# RADM-Connector-S05-V00.net
KiCad netlist of a schematic drawn in Altium Designer
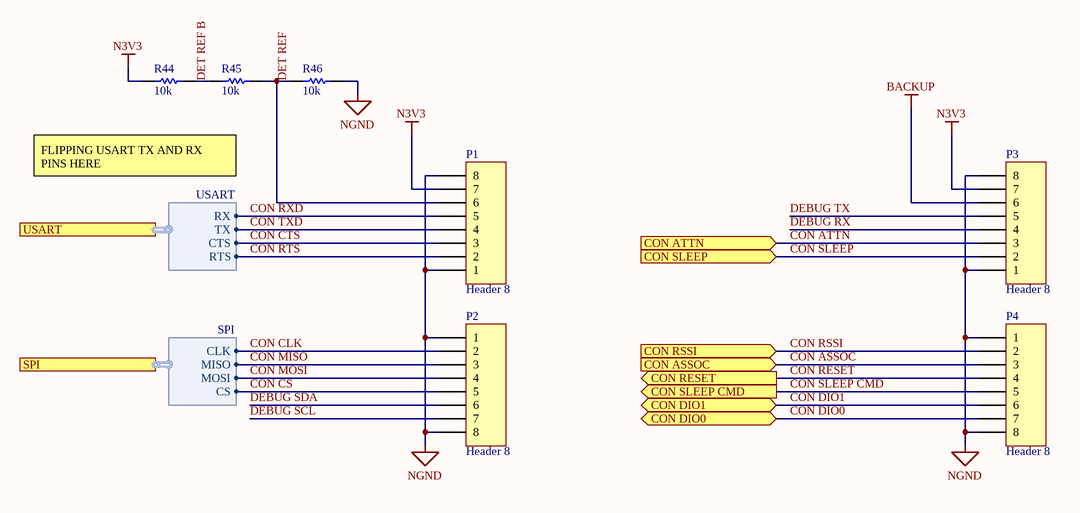
[diagram p0: RADM-Connector-S05-V00.SchDoc]

(export (version "E")
  (design (tool "Eeschema 10.0.6"))
  (components
    (comp (ref "P1")
      (value "Header 8")
      (footprint "HDR1X8")
      (description "Header, 8-Pin")
      (fields (field (name "PUBLISHER") "Altium Limited"))
      (libsource (lib "Miscellaneous Connectors") (part "Header 8"))
    )
    (comp (ref "P2")
      (value "Header 8")
      (footprint "HDR1X8")
      (description "Header, 8-Pin")
      (fields (field (name "PUBLISHER") "Altium Limited"))
      (libsource (lib "") (part "Header 8_1"))
    )
    (comp (ref "P3")
      (value "Header 8")
      (footprint "HDR1X8")
      (description "Header, 8-Pin")
      (fields (field (name "PUBLISHER") "Altium Limited"))
      (libsource (lib "Miscellaneous Connectors") (part "Header 8"))
    )
    (comp (ref "P4")
      (value "Header 8")
      (footprint "HDR1X8")
      (description "Header, 8-Pin")
      (fields (field (name "PUBLISHER") "Altium Limited"))
      (libsource (lib "") (part "Header 8_1"))
    )
    (comp (ref "R44")
      (value "10k")
      (footprint "Res_ThinFilm_0603")
      (description "Resistor, SMD, 10k, 0.1W, 5%, 0603")
      (libsource (lib "StandardResistors") (part "10k 5% 0603"))
    )
    (comp (ref "R45")
      (value "10k")
      (footprint "Res_ThinFilm_0603")
      (description "Resistor, SMD, 10k, 0.1W, 5%, 0603")
      (libsource (lib "StandardResistors") (part "10k 5% 0603"))
    )
    (comp (ref "R46")
      (value "10k")
      (footprint "Res_ThinFilm_0603")
      (description "Resistor, SMD, 10k, 0.1W, 5%, 0603")
      (libsource (lib "StandardResistors") (part "10k 5% 0603"))
    )
  )
  (nets
    (net (code "3") (name "/CON ASSOC") (class "Default")
      (node (ref "P4") (pin "3") (pinfunction "3_3") (pintype "passive"))
    )
    (net (code "4") (name "/CON ATTN") (class "Default")
      (node (ref "P3") (pin "3") (pinfunction "3_3") (pintype "passive"))
    )
    (net (code "5") (name "/CON CLK") (class "Default")
      (node (ref "P2") (pin "2") (pinfunction "2_2") (pintype "passive"))
    )
    (net (code "6") (name "/CON CS") (class "Default")
      (node (ref "P2") (pin "5") (pinfunction "5_5") (pintype "passive"))
    )
    (net (code "7") (name "/CON CTS") (class "Default")
      (node (ref "P1") (pin "3") (pinfunction "3_3") (pintype "passive"))
    )
    (net (code "8") (name "/CON DIO0") (class "Default")
      (node (ref "P4") (pin "7") (pinfunction "7_7") (pintype "passive"))
    )
    (net (code "9") (name "/CON DIO1") (class "Default")
      (node (ref "P4") (pin "6") (pinfunction "6_6") (pintype "passive"))
    )
    (net (code "10") (name "/CON MISO") (class "Default")
      (node (ref "P2") (pin "3") (pinfunction "3_3") (pintype "passive"))
    )
    (net (code "11") (name "/CON MOSI") (class "Default")
      (node (ref "P2") (pin "4") (pinfunction "4_4") (pintype "passive"))
    )
    (net (code "12") (name "/CON RESET") (class "Default")
      (node (ref "P4") (pin "4") (pinfunction "4_4") (pintype "passive"))
    )
    (net (code "13") (name "/CON RSSI") (class "Default")
      (node (ref "P4") (pin "2") (pinfunction "2_2") (pintype "passive"))
    )
    (net (code "14") (name "/CON RTS") (class "Default")
      (node (ref "P1") (pin "2") (pinfunction "2_2") (pintype "passive"))
    )
    (net (code "15") (name "/CON RXD") (class "Default")
      (node (ref "P1") (pin "5") (pinfunction "5_5") (pintype "passive"))
    )
    (net (code "16") (name "/CON SLEEP") (class "Default")
      (node (ref "P3") (pin "2") (pinfunction "2_2") (pintype "passive"))
    )
    (net (code "17") (name "/CON SLEEP CMD") (class "Default")
      (node (ref "P4") (pin "5") (pinfunction "5_5") (pintype "passive"))
    )
    (net (code "18") (name "/CON TXD") (class "Default")
      (node (ref "P1") (pin "4") (pinfunction "4_4") (pintype "passive"))
    )
    (net (code "19") (name "/DEBUG RX") (class "Default")
      (node (ref "P3") (pin "4") (pinfunction "4_4") (pintype "passive"))
    )
    (net (code "20") (name "/DEBUG SCL") (class "Default")
      (node (ref "P2") (pin "7") (pinfunction "7_7") (pintype "passive"))
    )
    (net (code "21") (name "/DEBUG SDA") (class "Default")
      (node (ref "P2") (pin "6") (pinfunction "6_6") (pintype "passive"))
    )
    (net (code "22") (name "/DEBUG TX") (class "Default")
      (node (ref "P3") (pin "5") (pinfunction "5_5") (pintype "passive"))
    )
    (net (code "23") (name "/DET REF") (class "Default")
      (node (ref "P1") (pin "6") (pinfunction "6_6") (pintype "passive"))
      (node (ref "R45") (pin "2") (pinfunction "2_2") (pintype "passive"))
      (node (ref "R46") (pin "1") (pinfunction "1_1") (pintype "passive"))
    )
    (net (code "24") (name "/DET REF B") (class "Default")
      (node (ref "R44") (pin "2") (pinfunction "2_2") (pintype "passive"))
      (node (ref "R45") (pin "1") (pinfunction "1_1") (pintype "passive"))
    )
    (net (code "27") (name "BACKUP") (class "Default")
      (node (ref "P3") (pin "6") (pinfunction "6_6") (pintype "passive"))
    )
    (net (code "28") (name "N3V3") (class "Default")
      (node (ref "P1") (pin "7") (pinfunction "7_7") (pintype "passive"))
      (node (ref "P3") (pin "7") (pinfunction "7_7") (pintype "passive"))
      (node (ref "R44") (pin "1") (pinfunction "1_1") (pintype "passive"))
    )
    (net (code "29") (name "NGND") (class "Default")
      (node (ref "P1") (pin "1") (pinfunction "1_1") (pintype "passive"))
      (node (ref "P1") (pin "8") (pinfunction "8_8") (pintype "passive"))
      (node (ref "P2") (pin "1") (pinfunction "1_1") (pintype "passive"))
      (node (ref "P2") (pin "8") (pinfunction "8_8") (pintype "passive"))
      (node (ref "P3") (pin "1") (pinfunction "1_1") (pintype "passive"))
      (node (ref "P3") (pin "8") (pinfunction "8_8") (pintype "passive"))
      (node (ref "P4") (pin "1") (pinfunction "1_1") (pintype "passive"))
      (node (ref "P4") (pin "8") (pinfunction "8_8") (pintype "passive"))
      (node (ref "R46") (pin "2") (pinfunction "2_2") (pintype "passive"))
    )
  )
)
